# Slide_Switch.net
KiCad netlist of a schematic drawn in Altium Designer
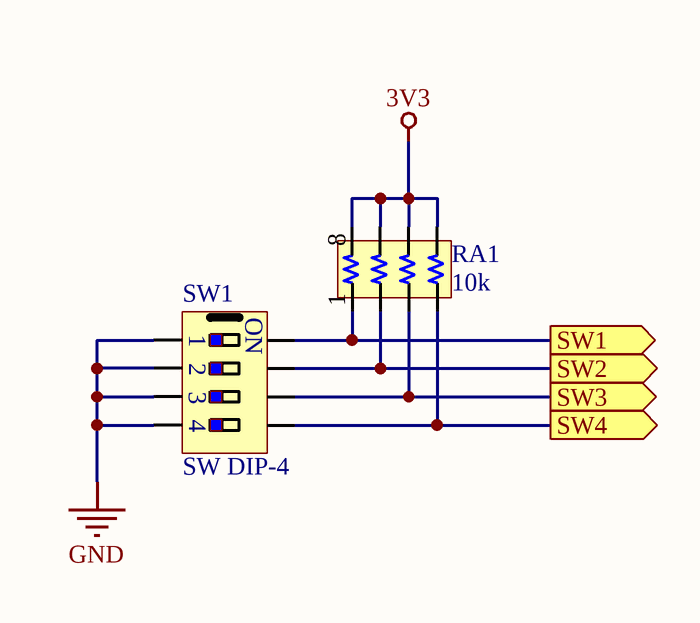
[diagram p0: Slide_Switch.SchDoc]

(export (version "E")
  (design (tool "Eeschema 10.0.6"))
  (components
    (comp (ref "RA1")
      (value "10k")
      (footprint "RA4 1206 (3216)")
      (description "Resistor Array 4")
      (libsource (lib "chipfc_altium_libs") (part "Resistor Array 4"))
    )
    (comp (ref "SW1")
      (value "SW DIP-4")
      (footprint "SW/DIP4")
      (libsource (lib "chipfc_altium_libs") (part "SW DIP-4"))
    )
  )
  (nets
    (net (code "1") (name "/SW1") (class "Default")
      (node (ref "RA1") (pin "1") (pinfunction "1_1") (pintype "passive"))
      (node (ref "SW1") (pin "8") (pinfunction "8_8") (pintype "passive"))
    )
    (net (code "2") (name "/SW2") (class "Default")
      (node (ref "RA1") (pin "2") (pinfunction "2_2") (pintype "passive"))
      (node (ref "SW1") (pin "7") (pinfunction "7_7") (pintype "passive"))
    )
    (net (code "3") (name "/SW3") (class "Default")
      (node (ref "RA1") (pin "3") (pinfunction "3_3") (pintype "passive"))
      (node (ref "SW1") (pin "6") (pinfunction "6_6") (pintype "passive"))
    )
    (net (code "4") (name "/SW4") (class "Default")
      (node (ref "RA1") (pin "4") (pinfunction "4_4") (pintype "passive"))
      (node (ref "SW1") (pin "5") (pinfunction "5_5") (pintype "passive"))
    )
    (net (code "5") (name "3V3") (class "Default")
      (node (ref "RA1") (pin "5") (pinfunction "5_5") (pintype "passive"))
      (node (ref "RA1") (pin "6") (pinfunction "6_6") (pintype "passive"))
      (node (ref "RA1") (pin "7") (pinfunction "7_7") (pintype "passive"))
      (node (ref "RA1") (pin "8") (pinfunction "8_8") (pintype "passive"))
    )
    (net (code "6") (name "GND") (class "Default")
      (node (ref "SW1") (pin "1") (pinfunction "1_1") (pintype "passive"))
      (node (ref "SW1") (pin "2") (pinfunction "2_2") (pintype "passive"))
      (node (ref "SW1") (pin "3") (pinfunction "3_3") (pintype "passive"))
      (node (ref "SW1") (pin "4") (pinfunction "4_4") (pintype "passive"))
    )
  )
)
